# subckt_-3V6_charge_pump.net
KiCad netlist of a schematic drawn in Altium Designer
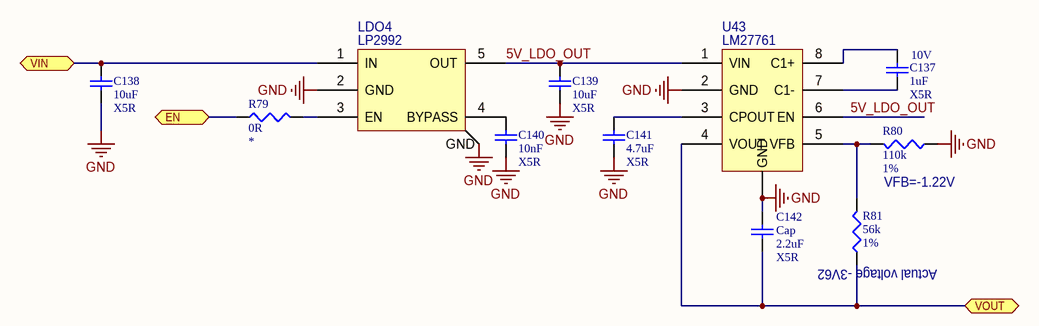
[diagram p0: subckt_-3V6_charge_pump.SchDoc]

(export (version "E")
  (design (tool "Eeschema 10.0.6"))
  (components
    (comp (ref "C137")
      (value "10V")
      (footprint "TBD")
      (description "Capacitor")
      (fields (field (name "ALTIUM_VALUE") "1uF") (field (name "DIELECTRIC") "X5R"))
      (libsource (lib "lib_basic") (part "Capacitor"))
    )
    (comp (ref "C138")
      (value "10uF")
      (footprint "TBD")
      (description "Capacitor")
      (fields (field (name "DIELECTRIC") "X5R"))
      (libsource (lib "lib_basic") (part "Capacitor"))
    )
    (comp (ref "C139")
      (value "10uF")
      (footprint "TBD")
      (description "Capacitor")
      (fields (field (name "DIELECTRIC") "X5R"))
      (libsource (lib "lib_basic") (part "Capacitor"))
    )
    (comp (ref "C140")
      (value "10nF")
      (footprint "TBD")
      (description "Capacitor")
      (fields (field (name "DIELECTRIC") "X5R"))
      (libsource (lib "lib_basic") (part "Capacitor"))
    )
    (comp (ref "C141")
      (value "4.7uF")
      (footprint "TBD")
      (description "Capacitor")
      (fields (field (name "DIELECTRIC") "X5R"))
      (libsource (lib "lib_basic") (part "Capacitor"))
    )
    (comp (ref "C142")
      (value "Cap")
      (footprint "TBD")
      (description "Capacitor")
      (fields (field (name "ALTIUM_VALUE") "2.2uF") (field (name "DIELECTRIC") "X5R"))
      (libsource (lib "lib_basic") (part "Capacitor"))
    )
    (comp (ref "LDO4")
      (value "LP2992")
      (description "LDO 5V 250mA")
      (libsource (lib "lib_TI_Power") (part "LP2992"))
    )
    (comp (ref "R79")
      (value "0R")
      (footprint "RES0603")
      (description "Resistor")
      (fields (field (name "TYPE") "*"))
      (libsource (lib "lib_basic") (part "Resistor"))
    )
    (comp (ref "R80")
      (value "110k")
      (footprint "RES0603")
      (description "Resistor")
      (fields (field (name "TYPE") "1%"))
      (libsource (lib "lib_basic") (part "Resistor"))
    )
    (comp (ref "R81")
      (value "56k")
      (footprint "RES0603")
      (description "Resistor")
      (fields (field (name "TYPE") "1%"))
      (libsource (lib "lib_basic") (part "Resistor"))
    )
    (comp (ref "U43")
      (value "LM27761")
      (description "Inverting charge pump w/ LDO, -1.5V to -5V")
      (libsource (lib "lib_TI_Power") (part "LM27761"))
    )
  )
  (nets
    (net (code "1") (name "/5V_LDO_OUT") (class "Default")
      (node (ref "C139") (pin "2") (pinfunction "2_2") (pintype "passive"))
      (node (ref "LDO4") (pin "5") (pinfunction "OUT_5") (pintype "passive"))
      (node (ref "U43") (pin "1") (pinfunction "VIN_1") (pintype "passive"))
      (node (ref "U43") (pin "6") (pinfunction "EN_6") (pintype "passive"))
    )
    (net (code "2") (name "/EN") (class "Default")
      (node (ref "R79") (pin "1") (pinfunction "1_1") (pintype "passive"))
    )
    (net (code "3") (name "/VIN") (class "Default")
      (node (ref "C138") (pin "2") (pinfunction "2_2") (pintype "passive"))
      (node (ref "LDO4") (pin "1") (pinfunction "IN_1") (pintype "passive"))
    )
    (net (code "4") (name "/VOUT") (class "Default")
      (node (ref "C142") (pin "2") (pinfunction "2_2") (pintype "passive"))
      (node (ref "R81") (pin "1") (pinfunction "1_1") (pintype "passive"))
      (node (ref "U43") (pin "4") (pinfunction "VOUT_4") (pintype "passive"))
    )
    (net (code "5") (name "GND") (class "Default")
      (node (ref "C138") (pin "1") (pinfunction "1_1") (pintype "passive"))
      (node (ref "C139") (pin "1") (pinfunction "1_1") (pintype "passive"))
      (node (ref "C140") (pin "1") (pinfunction "1_1") (pintype "passive"))
      (node (ref "C141") (pin "1") (pinfunction "1_1") (pintype "passive"))
      (node (ref "C142") (pin "1") (pinfunction "1_1") (pintype "passive"))
      (node (ref "LDO4") (pin "2") (pinfunction "GND_2") (pintype "passive"))
      (node (ref "LDO4") (pin "6") (pinfunction "GND_6") (pintype "passive"))
      (node (ref "R80") (pin "1") (pinfunction "1_1") (pintype "passive"))
      (node (ref "U43") (pin "2") (pinfunction "GND_2") (pintype "passive"))
      (node (ref "U43") (pin "9") (pinfunction "GND_9") (pintype "passive"))
    )
    (net (code "6") (name "Net-(LDO4-BYPASS)") (class "Default")
      (node (ref "C140") (pin "2") (pinfunction "2_2") (pintype "passive"))
      (node (ref "LDO4") (pin "4") (pinfunction "BYPASS_4") (pintype "passive"))
    )
    (net (code "7") (name "Net-(LDO4-EN)") (class "Default")
      (node (ref "LDO4") (pin "3") (pinfunction "EN_3") (pintype "passive"))
      (node (ref "R79") (pin "2") (pinfunction "2_2") (pintype "passive"))
    )
    (net (code "8") (name "Net-(U43-C1+)") (class "Default")
      (node (ref "C137") (pin "2") (pinfunction "2_2") (pintype "passive"))
      (node (ref "U43") (pin "8") (pinfunction "C1+_8") (pintype "passive"))
    )
    (net (code "9") (name "Net-(U43-C1-)") (class "Default")
      (node (ref "C137") (pin "1") (pinfunction "1_1") (pintype "passive"))
      (node (ref "U43") (pin "7") (pinfunction "C1-_7") (pintype "passive"))
    )
    (net (code "10") (name "Net-(U43-CPOUT)") (class "Default")
      (node (ref "C141") (pin "2") (pinfunction "2_2") (pintype "passive"))
      (node (ref "U43") (pin "3") (pinfunction "CPOUT_3") (pintype "passive"))
    )
    (net (code "11") (name "Net-(U43-VFB)") (class "Default")
      (node (ref "R80") (pin "2") (pinfunction "2_2") (pintype "passive"))
      (node (ref "R81") (pin "2") (pinfunction "2_2") (pintype "passive"))
      (node (ref "U43") (pin "5") (pinfunction "VFB_5") (pintype "passive"))
    )
  )
)
